# TAG_connect.net
KiCad netlist of a schematic drawn in EAGLE
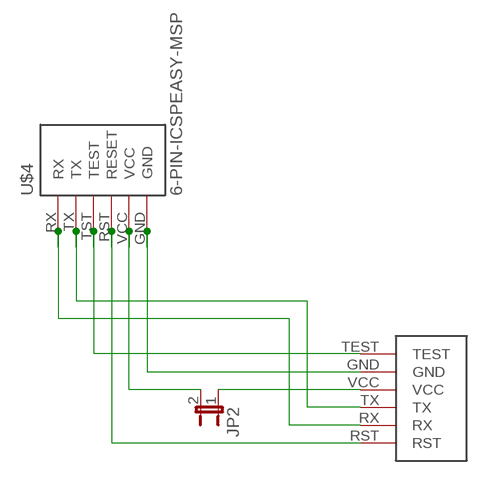
[diagram p0: schematic, sheet 1]

(export (version "E")
  (design (tool "Eeschema 10.0.6"))
  (components
    (comp (ref "JP2")
      (value "JUMPER-2PTH_LOCK")
      (footprint "eagle-import:1X02_LOCK")
      (libsource (lib "eagle-import") (part "JUMPER-2PTH_LOCK"))
    )
    (comp (ref "U$1")
      (value "RJ-45SMD")
      (footprint "eagle-import:MOLEX_RJ45_SMD")
      (libsource (lib "eagle-import") (part "RJ-45SMD"))
    )
    (comp (ref "U$4")
      (value "6-PIN-ICSPEASY-MSP")
      (footprint "eagle-import:EASYMSP-6PIN")
      (libsource (lib "eagle-import") (part "6-PIN-ICSPEASY-MSP"))
    )
  )
  (nets
    (net (code "1") (name "Net-(JP2-Pad1)") (class "Default")
      (node (ref "JP2") (pin "1") (pinfunction "1_1") (pintype "passive"))
      (node (ref "U$1") (pin "VCC") (pinfunction "VCC_VCC") (pintype "bidirectional"))
    )
    (net (code "2") (name "Net-(JP2-Pad2)") (class "Default")
      (node (ref "JP2") (pin "2") (pinfunction "2_2") (pintype "passive"))
      (node (ref "U$4") (pin "VCC") (pinfunction "VCC_VCC") (pintype "bidirectional"))
    )
    (net (code "3") (name "Net-(U$1-PadGND)") (class "Default")
      (node (ref "U$1") (pin "GND") (pinfunction "GND_GND") (pintype "bidirectional"))
      (node (ref "U$4") (pin "GND") (pinfunction "GND_GND") (pintype "bidirectional"))
    )
    (net (code "4") (name "Net-(U$1-PadRX)") (class "Default")
      (node (ref "U$1") (pin "RX") (pinfunction "RX_RX") (pintype "bidirectional"))
      (node (ref "U$4") (pin "RX") (pinfunction "RX_RX") (pintype "bidirectional"))
    )
    (net (code "5") (name "Net-(U$1-PadTX)") (class "Default")
      (node (ref "U$1") (pin "TX") (pinfunction "TX_TX") (pintype "bidirectional"))
      (node (ref "U$4") (pin "TX") (pinfunction "TX_TX") (pintype "bidirectional"))
    )
    (net (code "6") (name "Net-(U$4-RESET)") (class "Default")
      (node (ref "U$1") (pin "RST") (pinfunction "RST_RST") (pintype "bidirectional"))
      (node (ref "U$4") (pin "RST") (pinfunction "RESET_RST") (pintype "bidirectional"))
    )
    (net (code "7") (name "Net-(U$4-TEST)") (class "Default")
      (node (ref "U$1") (pin "TEST") (pinfunction "TEST_TEST") (pintype "bidirectional"))
      (node (ref "U$4") (pin "TST") (pinfunction "TEST_TST") (pintype "bidirectional"))
    )
  )
)
